# AVCC.net
KiCad netlist of a schematic drawn in Altium Designer
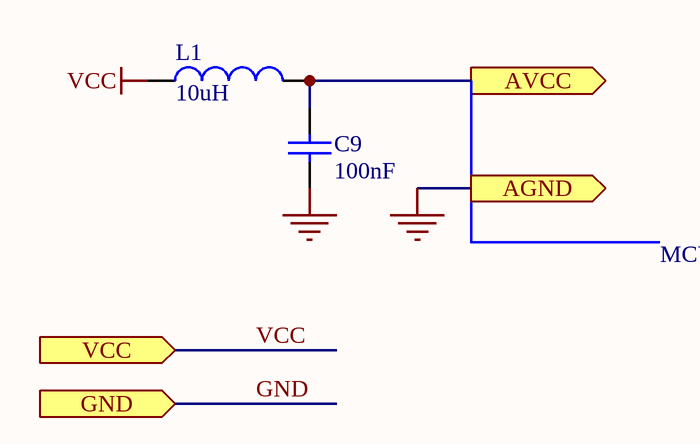
[diagram p0: AVCC.SchDoc]

(export (version "E")
  (design (tool "Eeschema 10.0.6"))
  (components
    (comp (ref "C9")
      (value "100nF")
      (footprint "RAD_2.54mm")
      (description "Capacitor")
      (fields
        (field (name "MANUFACTURER") "Generic Components")
        (field (name "Comment") "Capacitor_2")
        (field (name "PUBLISHER") "Altium Limited")
      )
      (libsource (lib "my Libraries") (part "Capacitor_2"))
    )
    (comp (ref "L1")
      (value "10uH")
      (footprint "Inductor_Axial")
      (description "Inductor")
      (fields (field (name "MANUFACTURER") "Generic Components") (field (name "PUBLISHER") "Altium Limited"))
      (libsource (lib "Miscellaneous Devices") (part "Inductor"))
    )
  )
  (nets
    (net (code "1") (name "/AVCC") (class "Default")
      (node (ref "C9") (pin "2") (pinfunction "2_2") (pintype "passive"))
      (node (ref "L1") (pin "2") (pinfunction "2_2") (pintype "passive"))
    )
    (net (code "2") (name "GND") (class "Default")
      (node (ref "C9") (pin "1") (pinfunction "1_1") (pintype "passive"))
    )
    (net (code "3") (name "VCC") (class "Default")
      (node (ref "L1") (pin "1") (pinfunction "1_1") (pintype "passive"))
    )
  )
)
